# 05_Connectors_Debug.net
KiCad netlist of a schematic drawn in Altium Designer
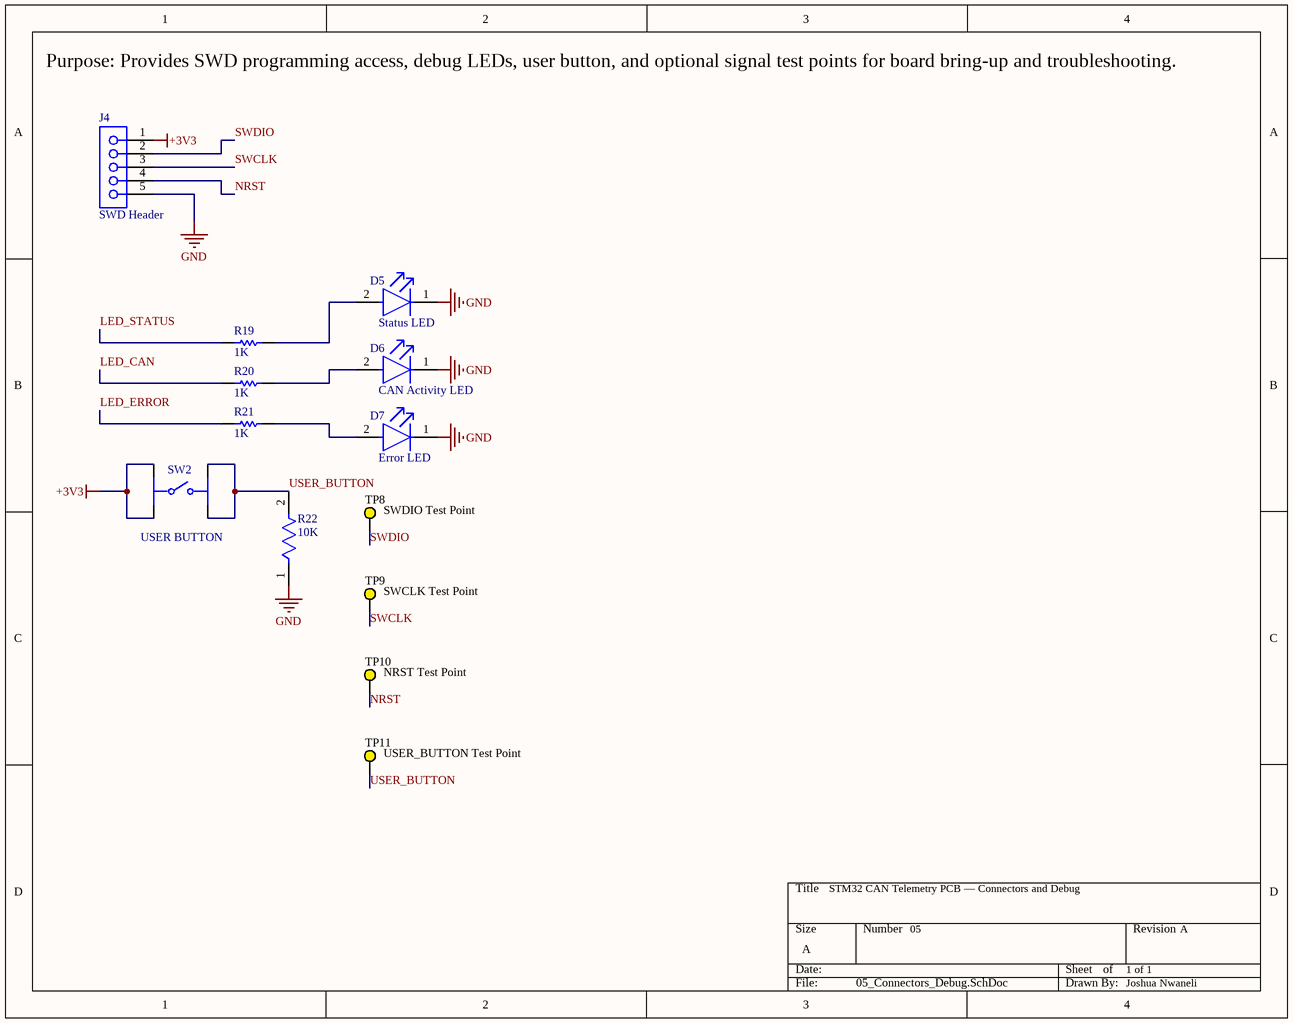
[diagram p0: 05_Connectors_Debug.SchDoc]

(export (version "E")
  (design (tool "Eeschema 10.0.6"))
  (components
    (comp (ref "D5")
      (value "Status LED")
      (footprint "FP-SML-LXT0805IW-TR-MFG")
      (description "LED RED DIFFUSED SMD")
      (libsource (lib "Altium Content Vault") (part "8706943c75ba83719d021d2fdc84c58"))
    )
    (comp (ref "D6")
      (value "CAN Activity LED")
      (footprint "FP-SML-LXT0805IW-TR-MFG")
      (description "LED RED DIFFUSED SMD")
      (libsource (lib "Altium Content Vault") (part "8706943c75ba83719d021d2fdc84c58"))
    )
    (comp (ref "D7")
      (value "Error LED")
      (footprint "FP-SML-LXT0805IW-TR-MFG")
      (description "LED RED DIFFUSED SMD")
      (libsource (lib "Altium Content Vault") (part "8706943c75ba83719d021d2fdc84c58"))
    )
    (comp (ref "J4")
      (value "SWD Header")
      (footprint "SMTC-SSW-105-01-X-S")
      (description "SQ Post Socket, Through-hole, Vertical, -55 to 105 degC, 2.54mm Pitch, 5-Pin, Female, RoHS")
      (fields (field (name "MANUFACTURER") "Samtec") (field (name "PARTNUMBER") "SSW-105-01-T-S"))
      (libsource (lib "Altium Content Vault") (part "SMTC-SSW-105-X-X-S"))
    )
    (comp (ref "R19")
      (value "1K")
      (footprint "RESC2013X50X30ML20T20")
      (fields (field (name "MANUFACTURER") "Vishay Dale") (field (name "PART NUMBER") "CRCW08051K00FKTC"))
      (libsource (lib "Altium Content Vault") (part "RES"))
    )
    (comp (ref "R20")
      (value "1K")
      (footprint "RESC2013X50X30ML20T20")
      (fields (field (name "MANUFACTURER") "Vishay Dale") (field (name "PART NUMBER") "CRCW08051K00FKTC"))
      (libsource (lib "Altium Content Vault") (part "RES"))
    )
    (comp (ref "R21")
      (value "1K")
      (footprint "RESC2013X50X30ML20T20")
      (fields (field (name "MANUFACTURER") "Vishay Dale") (field (name "PART NUMBER") "CRCW08051K00FKTC"))
      (libsource (lib "Altium Content Vault") (part "RES"))
    )
    (comp (ref "R22")
      (value "10K")
      (footprint "FP-CRGP0805-IPC_C")
      (description "CRGP0805 10KΩ 0.33W ±100ppm/°C 1% 150V")
      (fields (field (name "MANUFACTURER PART NUMBER") "CRGP0805F10K"))
      (libsource (lib "Altium Content Vault") (part "1029c3af85768c4190bb7ad29bc67b5"))
    )
    (comp (ref "SW2")
      (value "USER BUTTON")
      (footprint "FP-7914J-1-032-MFG")
      (description "Normally open user pushbutton input")
      (libsource (lib "Altium Content Vault") (part "31b61e1575766857d5d37af9ed38f2e"))
    )
    (comp (ref "TP8")
      (value "SWDIO Test Point")
      (footprint "KSTN-5014_V")
      (description "Test Point, Yellow, Through Hole, RoHS, Bulk")
      (fields (field (name "MANUFACTURER") "Keystone"))
      (libsource (lib "Altium Content Vault") (part "TESTPOINT_YELLOW"))
    )
    (comp (ref "TP9")
      (value "SWCLK Test Point")
      (footprint "KSTN-5014_V")
      (description "Test Point, Yellow, Through Hole, RoHS, Bulk")
      (fields (field (name "MANUFACTURER") "Keystone"))
      (libsource (lib "Altium Content Vault") (part "TESTPOINT_YELLOW"))
    )
    (comp (ref "TP10")
      (value "NRST Test Point")
      (footprint "KSTN-5014_V")
      (description "Test Point, Yellow, Through Hole, RoHS, Bulk")
      (fields (field (name "MANUFACTURER") "Keystone"))
      (libsource (lib "Altium Content Vault") (part "TESTPOINT_YELLOW"))
    )
    (comp (ref "TP11")
      (value "USER_BUTTON Test Point")
      (footprint "KSTN-5014_V")
      (description "Test Point, Yellow, Through Hole, RoHS, Bulk")
      (fields (field (name "MANUFACTURER") "Keystone"))
      (libsource (lib "Altium Content Vault") (part "TESTPOINT_YELLOW"))
    )
  )
  (nets
    (net (code "1") (name "+3V3") (class "Default")
      (node (ref "J4") (pin "1") (pinfunction "1_1") (pintype "passive"))
      (node (ref "SW2") (pin "1_1-") (pinfunction "1_1-_1_1-") (pintype "passive"))
      (node (ref "SW2") (pin "2_1-") (pinfunction "2_1-_2_1-") (pintype "passive"))
    )
    (net (code "2") (name "/LED_CAN") (class "Default")
      (node (ref "R20") (pin "1") (pinfunction "1_1") (pintype "passive"))
    )
    (net (code "3") (name "/LED_ERROR") (class "Default")
      (node (ref "R21") (pin "1") (pinfunction "1_1") (pintype "passive"))
    )
    (net (code "4") (name "/LED_STATUS") (class "Default")
      (node (ref "R19") (pin "1") (pinfunction "1_1") (pintype "passive"))
    )
    (net (code "5") (name "/NRST") (class "Default")
      (node (ref "J4") (pin "4") (pinfunction "4_4") (pintype "passive"))
      (node (ref "TP10") (pin "1") (pinfunction "1_1") (pintype "passive"))
    )
    (net (code "6") (name "/SWCLK") (class "Default")
      (node (ref "J4") (pin "3") (pinfunction "3_3") (pintype "passive"))
      (node (ref "TP9") (pin "1") (pinfunction "1_1") (pintype "passive"))
    )
    (net (code "7") (name "/SWDIO") (class "Default")
      (node (ref "J4") (pin "2") (pinfunction "2_2") (pintype "passive"))
      (node (ref "TP8") (pin "1") (pinfunction "1_1") (pintype "passive"))
    )
    (net (code "8") (name "/USER_BUTTON") (class "Default")
      (node (ref "R22") (pin "2") (pinfunction "2_2") (pintype "passive"))
      (node (ref "SW2") (pin "1_2+") (pinfunction "1_2+_1_2+") (pintype "passive"))
      (node (ref "SW2") (pin "2_2+") (pinfunction "2_2+_2_2+") (pintype "passive"))
      (node (ref "TP11") (pin "1") (pinfunction "1_1") (pintype "passive"))
    )
    (net (code "9") (name "GND") (class "Default")
      (node (ref "D5") (pin "1") (pinfunction "C_1") (pintype "passive"))
      (node (ref "D6") (pin "1") (pinfunction "C_1") (pintype "passive"))
      (node (ref "D7") (pin "1") (pinfunction "C_1") (pintype "passive"))
      (node (ref "J4") (pin "5") (pinfunction "5_5") (pintype "passive"))
      (node (ref "R22") (pin "1") (pinfunction "1_1") (pintype "passive"))
    )
    (net (code "10") (name "Net-(D5-A)") (class "Default")
      (node (ref "D5") (pin "2") (pinfunction "A_2") (pintype "passive"))
      (node (ref "R19") (pin "2") (pinfunction "2_2") (pintype "passive"))
    )
    (net (code "11") (name "Net-(D6-A)") (class "Default")
      (node (ref "D6") (pin "2") (pinfunction "A_2") (pintype "passive"))
      (node (ref "R20") (pin "2") (pinfunction "2_2") (pintype "passive"))
    )
    (net (code "12") (name "Net-(D7-A)") (class "Default")
      (node (ref "D7") (pin "2") (pinfunction "A_2") (pintype "passive"))
      (node (ref "R21") (pin "2") (pinfunction "2_2") (pintype "passive"))
    )
  )
)
